# NRF_module_for_band.net
KiCad netlist of a schematic drawn in Altium Designer
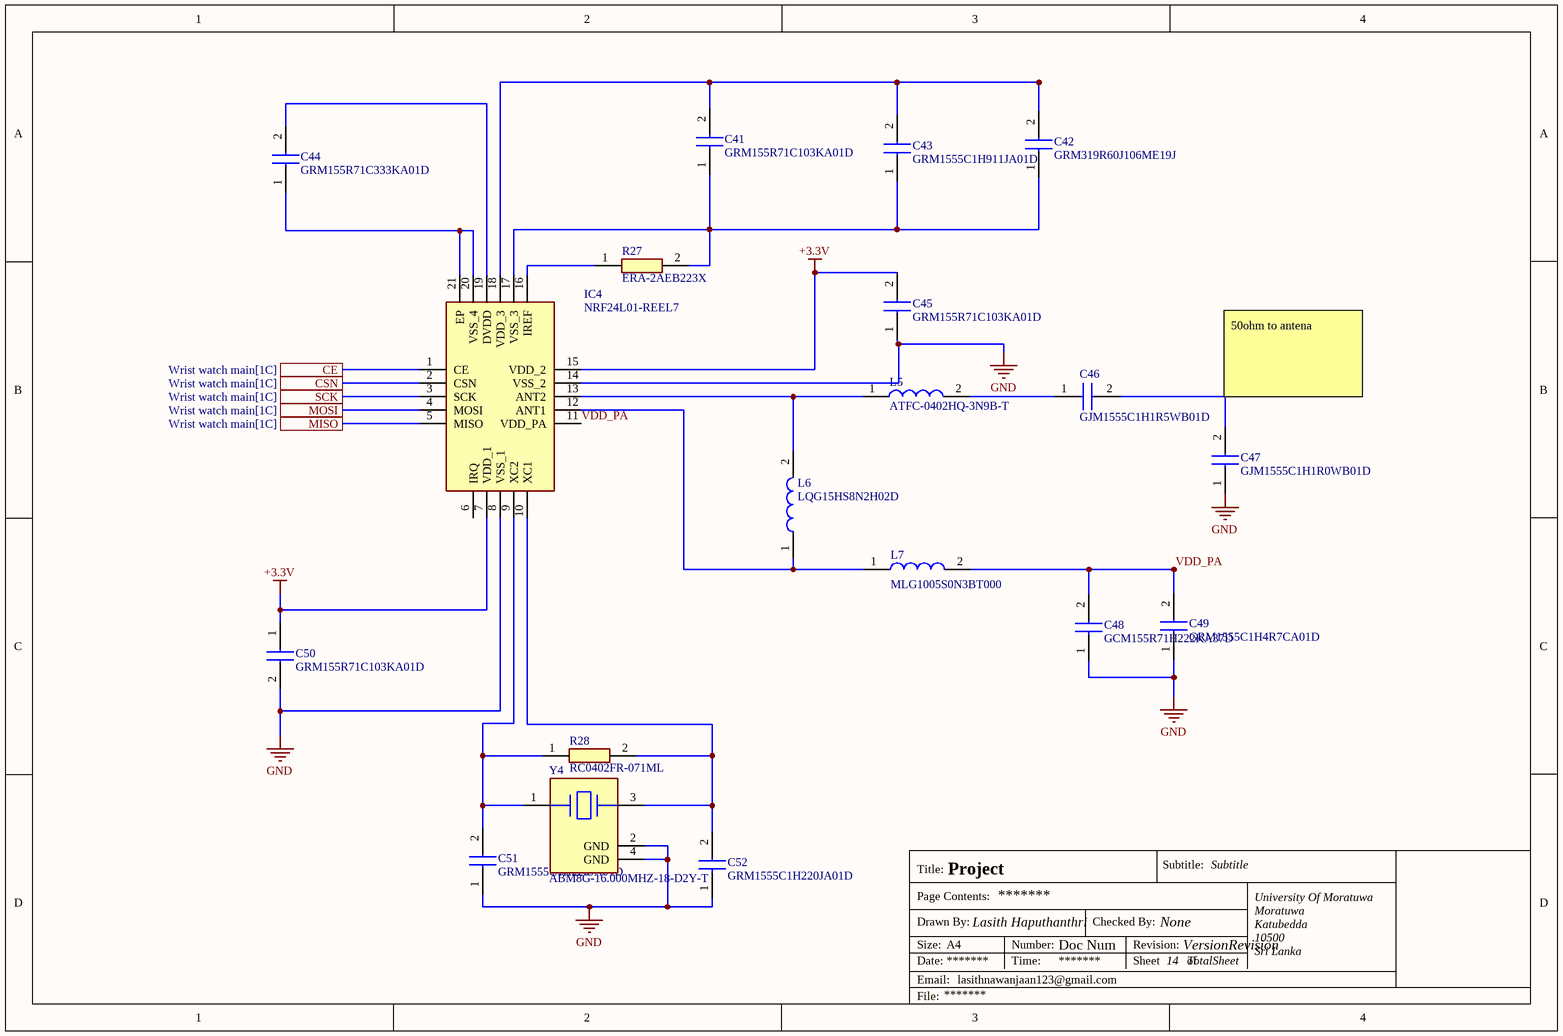
[diagram p0: NRF module for band.SchDoc]

(export (version "E")
  (design (tool "Eeschema 10.0.6"))
  (components
    (comp (ref "C41")
      (value "GRM155R71C103KA01D")
      (footprint "SamacSys:CAPC1005X55N")
      (description "Capacitor")
      (fields (field (name "MOUSER PART NUMBER") "81-GRM36X103K16"))
      (libsource (lib "*") (part "GRM155R71C103KA01D"))
    )
    (comp (ref "C42")
      (value "GRM319R60J106ME19J")
      (footprint "SamacSys:CAPC3216X95N")
      (description "Capacitor")
      (fields (field (name "MOUSER PART NUMBER") "81-GRM319R60J106ME9J"))
      (libsource (lib "*") (part "GRM319R60J106ME19J"))
    )
    (comp (ref "C43")
      (value "GRM1555C1H911JA01D")
      (footprint "SamacSys:CAPC1005X55N")
      (description "Capacitor")
      (fields (field (name "MOUSER PART NUMBER") "81-GRM1555C1H911JA1D"))
      (libsource (lib "*") (part "GRM1555C1H911JA01D"))
    )
    (comp (ref "C44")
      (value "GRM155R71C333KA01D")
      (footprint "SamacSys:CAPC1005X55N")
      (description "Capacitor")
      (libsource (lib "*") (part "GRM155R71C333KA01D"))
    )
    (comp (ref "C45")
      (value "GRM155R71C103KA01D")
      (footprint "SamacSys:CAPC1005X55N")
      (description "Capacitor")
      (fields (field (name "MOUSER PART NUMBER") "81-GRM36X103K16"))
      (libsource (lib "*") (part "GRM155R71C103KA01D"))
    )
    (comp (ref "C46")
      (value "GJM1555C1H1R5WB01D")
      (footprint "SamacSys:CAPC1005X55N")
      (description "Capacitor")
      (fields (field (name "MOUSER PART NUMBER") "81-GJM1555C1H1R5WB1D"))
      (libsource (lib "*") (part "GJM1555C1H1R5WB01D"))
    )
    (comp (ref "C47")
      (value "GJM1555C1H1R0WB01D")
      (footprint "SamacSys:CAPC1005X55N")
      (description "Capacitor")
      (fields (field (name "MOUSER PART NUMBER") "81-GJM1555C1H1R0WB1D"))
      (libsource (lib "*") (part "GJM1555C1H1R0WB01D"))
    )
    (comp (ref "C48")
      (value "GCM155R71H222KA37D")
      (footprint "SamacSys:CAPC1005X55N")
      (description "Capacitor")
      (fields (field (name "MOUSER PART NUMBER") "81-GCM155R71H222K37D"))
      (libsource (lib "*") (part "GCM155R71H222KA37D"))
    )
    (comp (ref "C49")
      (value "GRM1555C1H4R7CA01D")
      (footprint "SamacSys:CAPC1005X55N")
      (description "Capacitor")
      (fields (field (name "MOUSER PART NUMBER") "81-GRM1555C1H4R7CA1D"))
      (libsource (lib "*") (part "GRM1555C1H4R7CA01D"))
    )
    (comp (ref "C50")
      (value "GRM155R71C103KA01D")
      (footprint "SamacSys:CAPC1005X55N")
      (description "Capacitor")
      (fields (field (name "MOUSER PART NUMBER") "81-GRM36X103K16"))
      (libsource (lib "*") (part "GRM155R71C103KA01D"))
    )
    (comp (ref "C51")
      (value "GRM1555C1H220JA01D")
      (footprint "SamacSys:CAPC1005X55N")
      (description "Capacitor")
      (fields (field (name "MOUSER PART NUMBER") "81-GRM1555C1H220JA1D"))
      (libsource (lib "*") (part "GRM1555C1H220JA01D"))
    )
    (comp (ref "C52")
      (value "GRM1555C1H220JA01D")
      (footprint "SamacSys:CAPC1005X55N")
      (description "Capacitor")
      (fields (field (name "MOUSER PART NUMBER") "81-GRM1555C1H220JA1D"))
      (libsource (lib "*") (part "GRM1555C1H220JA01D"))
    )
    (comp (ref "IC4")
      (value "NRF24L01-REEL7")
      (footprint "SamacSys:QFN50P400X400X80-21N-D")
      (description "Integrated Circuit")
      (fields (field (name "MOUSER PART NUMBER") "949-NRF24L01-REEL7"))
      (libsource (lib "*") (part "NRF24L01-REEL7"))
    )
    (comp (ref "L5")
      (value "ATFC-0402HQ-3N9B-T")
      (footprint "SamacSys:INDC1005X37N")
      (description "Inductor")
      (libsource (lib "*") (part "ATFC-0402HQ-3N9B-T"))
    )
    (comp (ref "L6")
      (value "LQG15HS8N2H02D")
      (footprint "SamacSys:LQG15WH0N7B02D")
      (description "Inductor")
      (fields (field (name "MOUSER PART NUMBER") "81-LQG15HS8N2H02D"))
      (libsource (lib "*") (part "LQG15HS8N2H02D"))
    )
    (comp (ref "L7")
      (value "MLG1005S0N3BT000")
      (footprint "SamacSys:MLG1005")
      (description "Inductor")
      (fields (field (name "MOUSER PART NUMBER") "810-MLG1005S0N3BT000"))
      (libsource (lib "*") (part "MLG1005S0N3BT000"))
    )
    (comp (ref "R27")
      (value "ERA-2AEB223X")
      (footprint "SamacSys:ERA2AED122X")
      (description "Resistor")
      (fields (field (name "MOUSER PART NUMBER") "667-ERA-2AEB223X"))
      (libsource (lib "*") (part "ERA-2AEB223X"))
    )
    (comp (ref "R28")
      (value "RC0402FR-071ML")
      (footprint "SamacSys:RESC1005X40N")
      (description "Resistor")
      (fields (field (name "MOUSER PART NUMBER") "603-RC0402FR-071ML"))
      (libsource (lib "*") (part "RC0402FR-071ML"))
    )
    (comp (ref "Y4")
      (value "ABM8G-16.000MHZ-18-D2Y-T")
      (footprint "FP-ABM8G-MFG")
      (description "Crystal 12MHz ±20ppm (Tol) ±30ppm (Stability) 18pF FUND 120Ω 4-Pin SMD T/R")
      (fields (field (name "TOLERANCE") "20ppm"))
      (libsource (lib "Altium Content Vault") (part "48e526d86b7f2615d98721063c72f49"))
    )
  )
  (nets
    (net (code "1") (name "+3.3V") (class "Default")
      (node (ref "C45") (pin "2") (pinfunction "2_2") (pintype "passive"))
      (node (ref "C50") (pin "1") (pinfunction "1_1") (pintype "passive"))
      (node (ref "IC4") (pin "15") (pinfunction "VDD_2_15") (pintype "passive"))
      (node (ref "IC4") (pin "7") (pinfunction "VDD_1_7") (pintype "passive"))
    )
    (net (code "2") (name "/CE") (class "Default")
      (node (ref "IC4") (pin "1") (pinfunction "CE_1") (pintype "passive"))
    )
    (net (code "3") (name "/CSN") (class "Default")
      (node (ref "IC4") (pin "2") (pinfunction "CSN_2") (pintype "passive"))
    )
    (net (code "4") (name "/MISO") (class "Default")
      (node (ref "IC4") (pin "5") (pinfunction "MISO_5") (pintype "passive"))
    )
    (net (code "5") (name "/MOSI") (class "Default")
      (node (ref "IC4") (pin "4") (pinfunction "MOSI_4") (pintype "passive"))
    )
    (net (code "6") (name "/SCK") (class "Default")
      (node (ref "IC4") (pin "3") (pinfunction "SCK_3") (pintype "passive"))
    )
    (net (code "7") (name "/VDD_PA") (class "Default")
      (node (ref "C48") (pin "2") (pinfunction "2_2") (pintype "passive"))
      (node (ref "C49") (pin "2") (pinfunction "2_2") (pintype "passive"))
      (node (ref "IC4") (pin "11") (pinfunction "VDD_PA_11") (pintype "passive"))
      (node (ref "L7") (pin "2") (pinfunction "2_2") (pintype "passive"))
    )
    (net (code "8") (name "GND") (class "Default")
      (node (ref "C45") (pin "1") (pinfunction "1_1") (pintype "passive"))
      (node (ref "C47") (pin "1") (pinfunction "1_1") (pintype "passive"))
      (node (ref "C48") (pin "1") (pinfunction "1_1") (pintype "passive"))
      (node (ref "C49") (pin "1") (pinfunction "1_1") (pintype "passive"))
      (node (ref "C50") (pin "2") (pinfunction "2_2") (pintype "passive"))
      (node (ref "C51") (pin "1") (pinfunction "1_1") (pintype "passive"))
      (node (ref "C52") (pin "1") (pinfunction "1_1") (pintype "passive"))
      (node (ref "IC4") (pin "14") (pinfunction "VSS_2_14") (pintype "passive"))
      (node (ref "IC4") (pin "8") (pinfunction "VSS_1_8") (pintype "passive"))
      (node (ref "Y4") (pin "2") (pinfunction "GND_2") (pintype "power_in"))
      (node (ref "Y4") (pin "4") (pinfunction "GND_4") (pintype "power_in"))
    )
    (net (code "9") (name "Net-(C46-Pad1)") (class "Default")
      (node (ref "C46") (pin "1") (pinfunction "1_1") (pintype "passive"))
      (node (ref "L5") (pin "2") (pinfunction "2_2") (pintype "passive"))
    )
    (net (code "10") (name "Net-(C46-Pad2)") (class "Default")
      (node (ref "C46") (pin "2") (pinfunction "2_2") (pintype "passive"))
      (node (ref "C47") (pin "2") (pinfunction "2_2") (pintype "passive"))
    )
    (net (code "11") (name "Net-(IC4-ANT1)") (class "Default")
      (node (ref "IC4") (pin "12") (pinfunction "ANT1_12") (pintype "passive"))
      (node (ref "L6") (pin "1") (pinfunction "1_1") (pintype "passive"))
      (node (ref "L7") (pin "1") (pinfunction "1_1") (pintype "passive"))
    )
    (net (code "12") (name "Net-(IC4-ANT2)") (class "Default")
      (node (ref "IC4") (pin "13") (pinfunction "ANT2_13") (pintype "passive"))
      (node (ref "L5") (pin "1") (pinfunction "1_1") (pintype "passive"))
      (node (ref "L6") (pin "2") (pinfunction "2_2") (pintype "passive"))
    )
    (net (code "13") (name "Net-(IC4-DVDD)") (class "Default")
      (node (ref "C44") (pin "2") (pinfunction "2_2") (pintype "passive"))
      (node (ref "IC4") (pin "19") (pinfunction "DVDD_19") (pintype "passive"))
    )
    (net (code "14") (name "Net-(IC4-EP)") (class "Default")
      (node (ref "C44") (pin "1") (pinfunction "1_1") (pintype "passive"))
      (node (ref "IC4") (pin "20") (pinfunction "VSS_4_20") (pintype "passive"))
      (node (ref "IC4") (pin "21") (pinfunction "EP_21") (pintype "passive"))
    )
    (net (code "15") (name "Net-(IC4-IREF)") (class "Default")
      (node (ref "IC4") (pin "16") (pinfunction "IREF_16") (pintype "passive"))
      (node (ref "R27") (pin "1") (pinfunction "1_1") (pintype "passive"))
    )
    (net (code "16") (name "Net-(IC4-VDD_3)") (class "Default")
      (node (ref "C41") (pin "2") (pinfunction "2_2") (pintype "passive"))
      (node (ref "C42") (pin "2") (pinfunction "2_2") (pintype "passive"))
      (node (ref "C43") (pin "2") (pinfunction "2_2") (pintype "passive"))
      (node (ref "IC4") (pin "18") (pinfunction "VDD_3_18") (pintype "passive"))
    )
    (net (code "17") (name "Net-(IC4-VSS_3)") (class "Default")
      (node (ref "C41") (pin "1") (pinfunction "1_1") (pintype "passive"))
      (node (ref "C42") (pin "1") (pinfunction "1_1") (pintype "passive"))
      (node (ref "C43") (pin "1") (pinfunction "1_1") (pintype "passive"))
      (node (ref "IC4") (pin "17") (pinfunction "VSS_3_17") (pintype "passive"))
      (node (ref "R27") (pin "2") (pinfunction "2_2") (pintype "passive"))
    )
    (net (code "18") (name "Net-(IC4-XC1)") (class "Default")
      (node (ref "C52") (pin "2") (pinfunction "2_2") (pintype "passive"))
      (node (ref "IC4") (pin "10") (pinfunction "XC1_10") (pintype "passive"))
      (node (ref "R28") (pin "2") (pinfunction "2_2") (pintype "passive"))
      (node (ref "Y4") (pin "3") (pinfunction "3_3") (pintype "passive"))
    )
    (net (code "19") (name "Net-(IC4-XC2)") (class "Default")
      (node (ref "C51") (pin "2") (pinfunction "2_2") (pintype "passive"))
      (node (ref "IC4") (pin "9") (pinfunction "XC2_9") (pintype "passive"))
      (node (ref "R28") (pin "1") (pinfunction "1_1") (pintype "passive"))
      (node (ref "Y4") (pin "1") (pinfunction "1_1") (pintype "passive"))
    )
    (net (code "20") (name "unconnected-(IC4-IRQ-Pad6)") (class "Default")
      (node (ref "IC4") (pin "6") (pinfunction "IRQ_6") (pintype "passive"))
    )
  )
)
